# 1_MIAN.net
KiCad netlist of a schematic drawn in Altium Designer
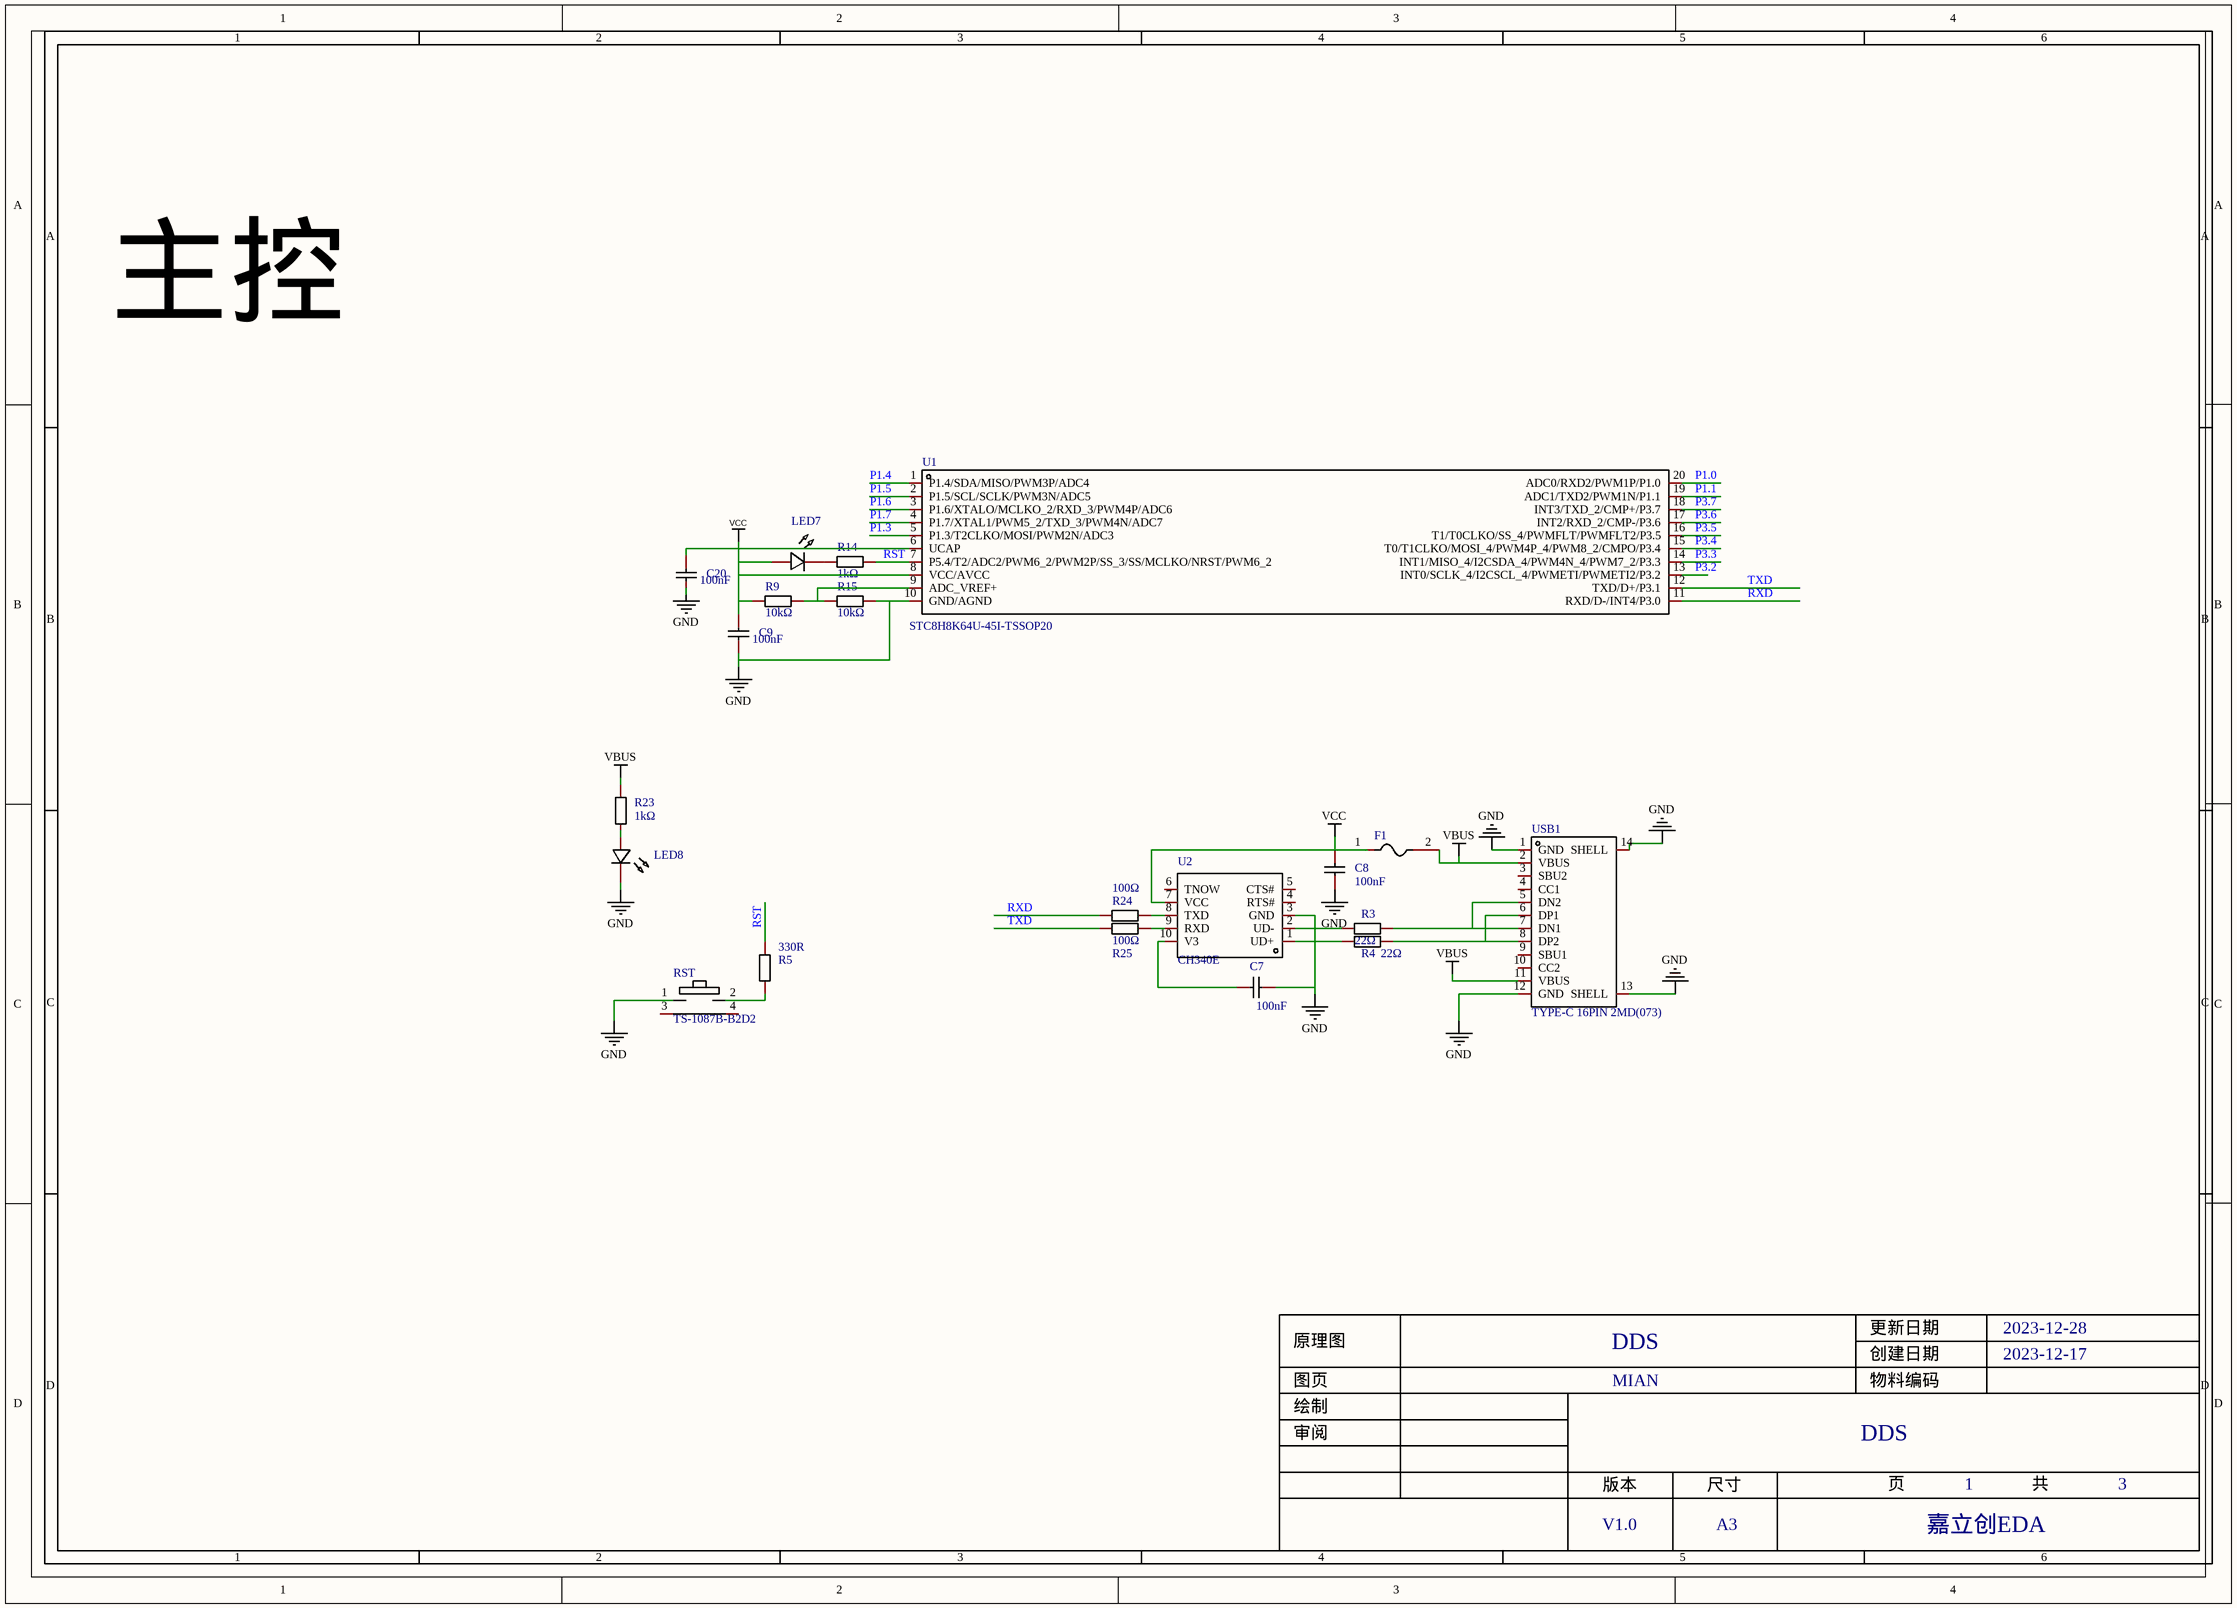
[diagram p0: 1_MIAN.schdoc]

(export (version "E")
  (design (tool "Eeschema 10.0.6"))
  (components
    (comp (ref "C7")
      (value "100nF")
      (description "容值:100nF;精度:±10%;额定电压:50V;材质(温度系数):X7R;")
      (fields
        (field (name "NAME") "100nF")
        (field (name "MANUFACTURER") "FH(风华)")
        (field (name "MANUFACTURER PART") "0805B104K500NT")
      )
      (libsource (lib "altium-import") (part "root_0_0805B104K500NT_"))
    )
    (comp (ref "C8")
      (value "100nF")
      (description "容值:100nF;精度:±10%;额定电压:50V;材质(温度系数):X7R;")
      (fields
        (field (name "NAME") "100nF")
        (field (name "MANUFACTURER") "FH(风华)")
        (field (name "MANUFACTURER PART") "0805B104K500NT")
      )
      (libsource (lib "altium-import") (part "root_3_mirrored_0805B104K500NT_"))
    )
    (comp (ref "C9")
      (value "100nF")
      (description "容值:100nF;精度:±10%;额定电压:50V;材质(温度系数):X7R;")
      (fields
        (field (name "NAME") "100nF")
        (field (name "MANUFACTURER") "FH(风华)")
        (field (name "MANUFACTURER PART") "0805B104K500NT")
      )
      (libsource (lib "altium-import") (part "root_1_0805B104K500NT_"))
    )
    (comp (ref "C20")
      (value "100nF")
      (description "容值:100nF;精度:±10%;额定电压:50V;材质(温度系数):X7R;")
      (fields
        (field (name "NAME") "100nF")
        (field (name "MANUFACTURER") "FH(风华)")
        (field (name "MANUFACTURER PART") "0805B104K500NT")
      )
      (libsource (lib "altium-import") (part "root_1_0805B104K500NT_"))
    )
    (comp (ref "F1")
      (value "nSMD010")
      (description "最大电压:60V;最大电流:40A;保持电流:100mA;跳闸电流:250mA;")
      (fields (field (name "MANUFACTURER") "台湾陆海"))
      (libsource (lib "altium-import") (part "root_0_nSMD010_"))
    )
    (comp (ref "LED7") (value "LED_B") (libsource (lib "altium-import") (part "root_0_LED_B_")))
    (comp (ref "LED8") (value "LED_B") (libsource (lib "altium-import") (part "root_3_LED_B_")))
    (comp (ref "R3")
      (value "22Ω")
      (description "阻值:1kΩ;精度:±1%;功率:125mW;温度系数:±100ppm/℃;电阻类型:厚膜电阻;")
      (fields
        (field (name "NAME") "22Ω")
        (field (name "MANUFACTURER") "UNI-ROYAL(厚声)")
        (field (name "MANUFACTURER PART") "0805W8F1001T5E")
      )
      (libsource (lib "altium-import") (part "root_0_0805W8F1001T5E_"))
    )
    (comp (ref "R4")
      (value "22Ω")
      (description "阻值:1kΩ;精度:±1%;功率:125mW;温度系数:±100ppm/℃;电阻类型:厚膜电阻;")
      (fields
        (field (name "NAME") "22Ω")
        (field (name "MANUFACTURER") "UNI-ROYAL(厚声)")
        (field (name "MANUFACTURER PART") "0805W8F1001T5E")
      )
      (libsource (lib "altium-import") (part "root_0_0805W8F1001T5E_"))
    )
    (comp (ref "R5")
      (value "330R")
      (description "阻值:1kΩ;精度:±1%;功率:125mW;温度系数:±100ppm/℃;电阻类型:厚膜电阻;")
      (fields
        (field (name "MANUFACTURER") "UNI-ROYAL(厚声)")
        (field (name "MANUFACTURER PART") "0805W8F1001T5E")
      )
      (libsource (lib "altium-import") (part "root_1_0805W8F1001T5E_"))
    )
    (comp (ref "R9")
      (value "10kΩ")
      (description "阻值:1kΩ;精度:±1%;功率:125mW;温度系数:±100ppm/℃;电阻类型:厚膜电阻;")
      (fields
        (field (name "NAME") "10kΩ")
        (field (name "MANUFACTURER") "UNI-ROYAL(厚声)")
        (field (name "MANUFACTURER PART") "0805W8F1001T5E")
      )
      (libsource (lib "altium-import") (part "root_0_0805W8F1001T5E_"))
    )
    (comp (ref "R14")
      (value "1kΩ")
      (description "阻值:1kΩ;精度:±1%;功率:125mW;温度系数:±100ppm/℃;电阻类型:厚膜电阻;")
      (fields
        (field (name "NAME") "1kΩ")
        (field (name "MANUFACTURER") "UNI-ROYAL(厚声)")
        (field (name "MANUFACTURER PART") "0805W8F1001T5E")
      )
      (libsource (lib "altium-import") (part "root_0_0805W8F1001T5E_"))
    )
    (comp (ref "R15")
      (value "10kΩ")
      (description "阻值:1kΩ;精度:±1%;功率:125mW;温度系数:±100ppm/℃;电阻类型:厚膜电阻;")
      (fields
        (field (name "NAME") "10kΩ")
        (field (name "MANUFACTURER") "UNI-ROYAL(厚声)")
        (field (name "MANUFACTURER PART") "0805W8F1001T5E")
      )
      (libsource (lib "altium-import") (part "root_0_0805W8F1001T5E_"))
    )
    (comp (ref "R23")
      (value "1kΩ")
      (description "阻值:1kΩ;精度:±1%;功率:125mW;温度系数:±100ppm/℃;电阻类型:厚膜电阻;")
      (fields
        (field (name "NAME") "1kΩ")
        (field (name "MANUFACTURER") "UNI-ROYAL(厚声)")
        (field (name "MANUFACTURER PART") "0805W8F1001T5E")
      )
      (libsource (lib "altium-import") (part "root_1_0805W8F1001T5E_"))
    )
    (comp (ref "R24")
      (value "100Ω")
      (description "阻值:1kΩ;精度:±1%;功率:125mW;温度系数:±100ppm/℃;电阻类型:厚膜电阻;")
      (fields
        (field (name "NAME") "100Ω")
        (field (name "MANUFACTURER") "UNI-ROYAL(厚声)")
        (field (name "MANUFACTURER PART") "0805W8F1001T5E")
      )
      (libsource (lib "altium-import") (part "root_0_0805W8F1001T5E_"))
    )
    (comp (ref "R25")
      (value "100Ω")
      (description "阻值:1kΩ;精度:±1%;功率:125mW;温度系数:±100ppm/℃;电阻类型:厚膜电阻;")
      (fields
        (field (name "NAME") "100Ω")
        (field (name "MANUFACTURER") "UNI-ROYAL(厚声)")
        (field (name "MANUFACTURER PART") "0805W8F1001T5E")
      )
      (libsource (lib "altium-import") (part "root_0_0805W8F1001T5E_"))
    )
    (comp (ref "RST")
      (value "TS-1087B-B2D2")
      (description "电路结构:单刀单掷;按钮作用方向:侧面触动;致动器样式:矩形按钮;照明颜色:-;作用力:180gf ±30gf;开关高度:3.5mm;")
      (fields (field (name "NAME") "TS-1087B-B2D2") (field (name "MANUFACTURER") "Yuandi(元迪)"))
      (libsource (lib "altium-import") (part "root_0_TS-1087B-B2D2_"))
    )
    (comp (ref "U1")
      (value "STC8H8K64U-45I-TSSOP20")
      (fields (field (name "NAME") "STC8H8K64U-45I-TSSOP20") (field (name "MANUFACTURER") "STC(宏晶)"))
      (libsource (lib "altium-import") (part "root_0_STC8H8K64U-45I-TSSOP20_"))
    )
    (comp (ref "U2")
      (value "CH340E")
      (description "应用功能:收发器;接口协议:USB 2.0;数据速率:2Mbps;")
      (fields (field (name "NAME") "CH340E") (field (name "MANUFACTURER") "WCH(南京沁恒)"))
      (libsource (lib "altium-import") (part "root_2_CH340E_"))
    )
    (comp (ref "USB1")
      (value "TYPE-C 16PIN 2MD(073)")
      (description "连接器类型:Type-C;标准:-;公母:母;触点数量:16P;端口数量:1;安装方式:卧贴;额定电流 - 电源:5A;工作温度范围:-25℃~+85℃;")
      (fields (field (name "NAME") "TYPE-C 16PIN 2MD(073)") (field (name "MANUFACTURER") "SHOU HAN(首韩)"))
      (libsource (lib "altium-import") (part "root_0_TYPE-C 16PIN 2MD(073)_"))
    )
  )
  (nets
    (net (code "1") (name "/P1.0") (class "Default")
      (node (ref "U1") (pin "20") (pinfunction "ADC0/RXD2/PWM1P/P1.0_20") (pintype "passive"))
    )
    (net (code "2") (name "/P1.1") (class "Default")
      (node (ref "U1") (pin "19") (pinfunction "ADC1/TXD2/PWM1N/P1.1_19") (pintype "passive"))
    )
    (net (code "3") (name "/P1.3") (class "Default")
      (node (ref "U1") (pin "5") (pinfunction "P1.3/T2CLKO/MOSI/PWM2N/ADC3_5") (pintype "passive"))
    )
    (net (code "4") (name "/P1.4") (class "Default")
      (node (ref "U1") (pin "1") (pinfunction "P1.4/SDA/MISO/PWM3P/ADC4_1") (pintype "passive"))
    )
    (net (code "5") (name "/P1.5") (class "Default")
      (node (ref "U1") (pin "2") (pinfunction "P1.5/SCL/SCLK/PWM3N/ADC5_2") (pintype "passive"))
    )
    (net (code "6") (name "/P1.6") (class "Default")
      (node (ref "U1") (pin "3") (pinfunction "P1.6/XTALO/MCLKO_2/RXD_3/PWM4P/ADC6_3") (pintype "passive"))
    )
    (net (code "7") (name "/P1.7") (class "Default")
      (node (ref "U1") (pin "4") (pinfunction "P1.7/XTAL1/PWM5_2/TXD_3/PWM4N/ADC7_4") (pintype "passive"))
    )
    (net (code "8") (name "/P3.2") (class "Default")
      (node (ref "U1") (pin "13") (pinfunction "INT0/SCLK_4/I2CSCL_4/PWMETI/PWMETI2/P3.2_13") (pintype "passive"))
    )
    (net (code "9") (name "/P3.3") (class "Default")
      (node (ref "U1") (pin "14") (pinfunction "INT1/MISO_4/I2CSDA_4/PWM4N_4/PWM7_2/P3.3_14") (pintype "passive"))
    )
    (net (code "10") (name "/P3.4") (class "Default")
      (node (ref "U1") (pin "15") (pinfunction "T0/T1CLKO/MOSI_4/PWM4P_4/PWM8_2/CMPO/P3.4_15") (pintype "passive"))
    )
    (net (code "11") (name "/P3.5") (class "Default")
      (node (ref "U1") (pin "16") (pinfunction "T1/T0CLKO/SS_4/PWMFLT/PWMFLT2/P3.5_16") (pintype "passive"))
    )
    (net (code "12") (name "/P3.6") (class "Default")
      (node (ref "U1") (pin "17") (pinfunction "INT2/RXD_2/CMP-/P3.6_17") (pintype "passive"))
    )
    (net (code "13") (name "/P3.7") (class "Default")
      (node (ref "U1") (pin "18") (pinfunction "INT3/TXD_2/CMP+/P3.7_18") (pintype "passive"))
    )
    (net (code "14") (name "/RST") (class "Default")
      (node (ref "R14") (pin "2") (pinfunction "2_2") (pintype "passive"))
      (node (ref "R5") (pin "2") (pinfunction "2_2") (pintype "passive"))
      (node (ref "U1") (pin "7") (pinfunction "P5.4/T2/ADC2/PWM6_2/PWM2P/SS_3/SS/MCLKO/NRST/PWM6_2_7") (pintype "passive"))
    )
    (net (code "15") (name "/RXD") (class "Default")
      (node (ref "R24") (pin "1") (pinfunction "1_1") (pintype "passive"))
      (node (ref "U1") (pin "11") (pinfunction "RXD/D-/INT4/P3.0_11") (pintype "passive"))
    )
    (net (code "16") (name "/TXD") (class "Default")
      (node (ref "R25") (pin "1") (pinfunction "1_1") (pintype "passive"))
      (node (ref "U1") (pin "12") (pinfunction "TXD/D+/P3.1_12") (pintype "passive"))
    )
    (net (code "17") (name "GND") (class "Default")
      (node (ref "C20") (pin "1") (pinfunction "1_1") (pintype "passive"))
      (node (ref "C7") (pin "2") (pinfunction "2_2") (pintype "passive"))
      (node (ref "C8") (pin "2") (pinfunction "2_2") (pintype "passive"))
      (node (ref "C9") (pin "1") (pinfunction "1_1") (pintype "passive"))
      (node (ref "LED8") (pin "1") (pinfunction "C_1") (pintype "passive"))
      (node (ref "R15") (pin "2") (pinfunction "2_2") (pintype "passive"))
      (node (ref "RST") (pin "1") (pinfunction "1_1") (pintype "passive"))
      (node (ref "U1") (pin "10") (pinfunction "GND/AGND_10") (pintype "passive"))
      (node (ref "U2") (pin "3") (pinfunction "GND_3") (pintype "passive"))
      (node (ref "USB1") (pin "1") (pinfunction "GND_1") (pintype "passive"))
      (node (ref "USB1") (pin "12") (pinfunction "GND_12") (pintype "passive"))
      (node (ref "USB1") (pin "13") (pinfunction "SHELL_13") (pintype "passive"))
      (node (ref "USB1") (pin "14") (pinfunction "SHELL_14") (pintype "passive"))
    )
    (net (code "18") (name "Net-(LED7-C)") (class "Default")
      (node (ref "LED7") (pin "1") (pinfunction "C_1") (pintype "passive"))
      (node (ref "R14") (pin "1") (pinfunction "1_1") (pintype "passive"))
    )
    (net (code "19") (name "Net-(LED8-A)") (class "Default")
      (node (ref "LED8") (pin "2") (pinfunction "A_2") (pintype "passive"))
      (node (ref "R23") (pin "1") (pinfunction "1_1") (pintype "passive"))
    )
    (net (code "20") (name "Net-(R5-Pad1)") (class "Default")
      (node (ref "R5") (pin "1") (pinfunction "1_1") (pintype "passive"))
      (node (ref "RST") (pin "2") (pinfunction "2_2") (pintype "passive"))
    )
    (net (code "21") (name "Net-(U1-ADC_VREF+)") (class "Default")
      (node (ref "R15") (pin "1") (pinfunction "1_1") (pintype "passive"))
      (node (ref "R9") (pin "2") (pinfunction "2_2") (pintype "passive"))
      (node (ref "U1") (pin "9") (pinfunction "ADC_VREF+_9") (pintype "passive"))
    )
    (net (code "22") (name "Net-(U1-UCAP)") (class "Default")
      (node (ref "C20") (pin "2") (pinfunction "2_2") (pintype "passive"))
      (node (ref "U1") (pin "6") (pinfunction "UCAP_6") (pintype "passive"))
    )
    (net (code "23") (name "Net-(U2-RXD)") (class "Default")
      (node (ref "R25") (pin "2") (pinfunction "2_2") (pintype "passive"))
      (node (ref "U2") (pin "9") (pinfunction "RXD_9") (pintype "passive"))
    )
    (net (code "24") (name "Net-(U2-TXD)") (class "Default")
      (node (ref "R24") (pin "2") (pinfunction "2_2") (pintype "passive"))
      (node (ref "U2") (pin "8") (pinfunction "TXD_8") (pintype "passive"))
    )
    (net (code "25") (name "Net-(U2-UD+)") (class "Default")
      (node (ref "R4") (pin "1") (pinfunction "1_1") (pintype "passive"))
      (node (ref "U2") (pin "1") (pinfunction "UD+_1") (pintype "passive"))
    )
    (net (code "26") (name "Net-(U2-UD-)") (class "Default")
      (node (ref "R3") (pin "1") (pinfunction "1_1") (pintype "passive"))
      (node (ref "U2") (pin "2") (pinfunction "UD-_2") (pintype "passive"))
    )
    (net (code "27") (name "Net-(U2-V3)") (class "Default")
      (node (ref "C7") (pin "1") (pinfunction "1_1") (pintype "passive"))
      (node (ref "U2") (pin "10") (pinfunction "V3_10") (pintype "passive"))
    )
    (net (code "28") (name "Net-(USB1-DN1)") (class "Default")
      (node (ref "R3") (pin "2") (pinfunction "2_2") (pintype "passive"))
      (node (ref "USB1") (pin "5") (pinfunction "DN2_5") (pintype "passive"))
      (node (ref "USB1") (pin "7") (pinfunction "DN1_7") (pintype "passive"))
    )
    (net (code "29") (name "Net-(USB1-DP1)") (class "Default")
      (node (ref "R4") (pin "2") (pinfunction "2_2") (pintype "passive"))
      (node (ref "USB1") (pin "6") (pinfunction "DP1_6") (pintype "passive"))
      (node (ref "USB1") (pin "8") (pinfunction "DP2_8") (pintype "passive"))
    )
    (net (code "30") (name "VBUS") (class "Default")
      (node (ref "F1") (pin "2") (pinfunction "2_2") (pintype "passive"))
      (node (ref "R23") (pin "2") (pinfunction "2_2") (pintype "passive"))
      (node (ref "USB1") (pin "11") (pinfunction "VBUS_11") (pintype "passive"))
      (node (ref "USB1") (pin "2") (pinfunction "VBUS_2") (pintype "passive"))
    )
    (net (code "31") (name "VCC") (class "Default")
      (node (ref "C8") (pin "1") (pinfunction "1_1") (pintype "passive"))
      (node (ref "C9") (pin "2") (pinfunction "2_2") (pintype "passive"))
      (node (ref "F1") (pin "1") (pinfunction "1_1") (pintype "passive"))
      (node (ref "LED7") (pin "2") (pinfunction "A_2") (pintype "passive"))
      (node (ref "R9") (pin "1") (pinfunction "1_1") (pintype "passive"))
      (node (ref "U1") (pin "8") (pinfunction "VCC/AVCC_8") (pintype "passive"))
      (node (ref "U2") (pin "7") (pinfunction "VCC_7") (pintype "passive"))
    )
    (net (code "32") (name "unconnected-(RST-Pad3)") (class "Default")
      (node (ref "RST") (pin "3") (pinfunction "3_3") (pintype "passive"))
    )
    (net (code "33") (name "unconnected-(RST-Pad4)") (class "Default")
      (node (ref "RST") (pin "4") (pinfunction "4_4") (pintype "passive"))
    )
    (net (code "34") (name "unconnected-(U2-CTS#-Pad5)") (class "Default")
      (node (ref "U2") (pin "5") (pinfunction "CTS#_5") (pintype "passive"))
    )
    (net (code "35") (name "unconnected-(U2-RTS#-Pad4)") (class "Default")
      (node (ref "U2") (pin "4") (pinfunction "RTS#_4") (pintype "passive"))
    )
    (net (code "36") (name "unconnected-(U2-TNOW-Pad6)") (class "Default")
      (node (ref "U2") (pin "6") (pinfunction "TNOW_6") (pintype "passive"))
    )
    (net (code "37") (name "unconnected-(USB1-CC1-Pad4)") (class "Default")
      (node (ref "USB1") (pin "4") (pinfunction "CC1_4") (pintype "passive"))
    )
    (net (code "38") (name "unconnected-(USB1-CC2-Pad10)") (class "Default")
      (node (ref "USB1") (pin "10") (pinfunction "CC2_10") (pintype "passive"))
    )
    (net (code "39") (name "unconnected-(USB1-SBU1-Pad9)") (class "Default")
      (node (ref "USB1") (pin "9") (pinfunction "SBU1_9") (pintype "passive"))
    )
    (net (code "40") (name "unconnected-(USB1-SBU2-Pad3)") (class "Default")
      (node (ref "USB1") (pin "3") (pinfunction "SBU2_3") (pintype "passive"))
    )
  )
)
